# MBoard.net
KiCad netlist of a schematic drawn in Altium Designer
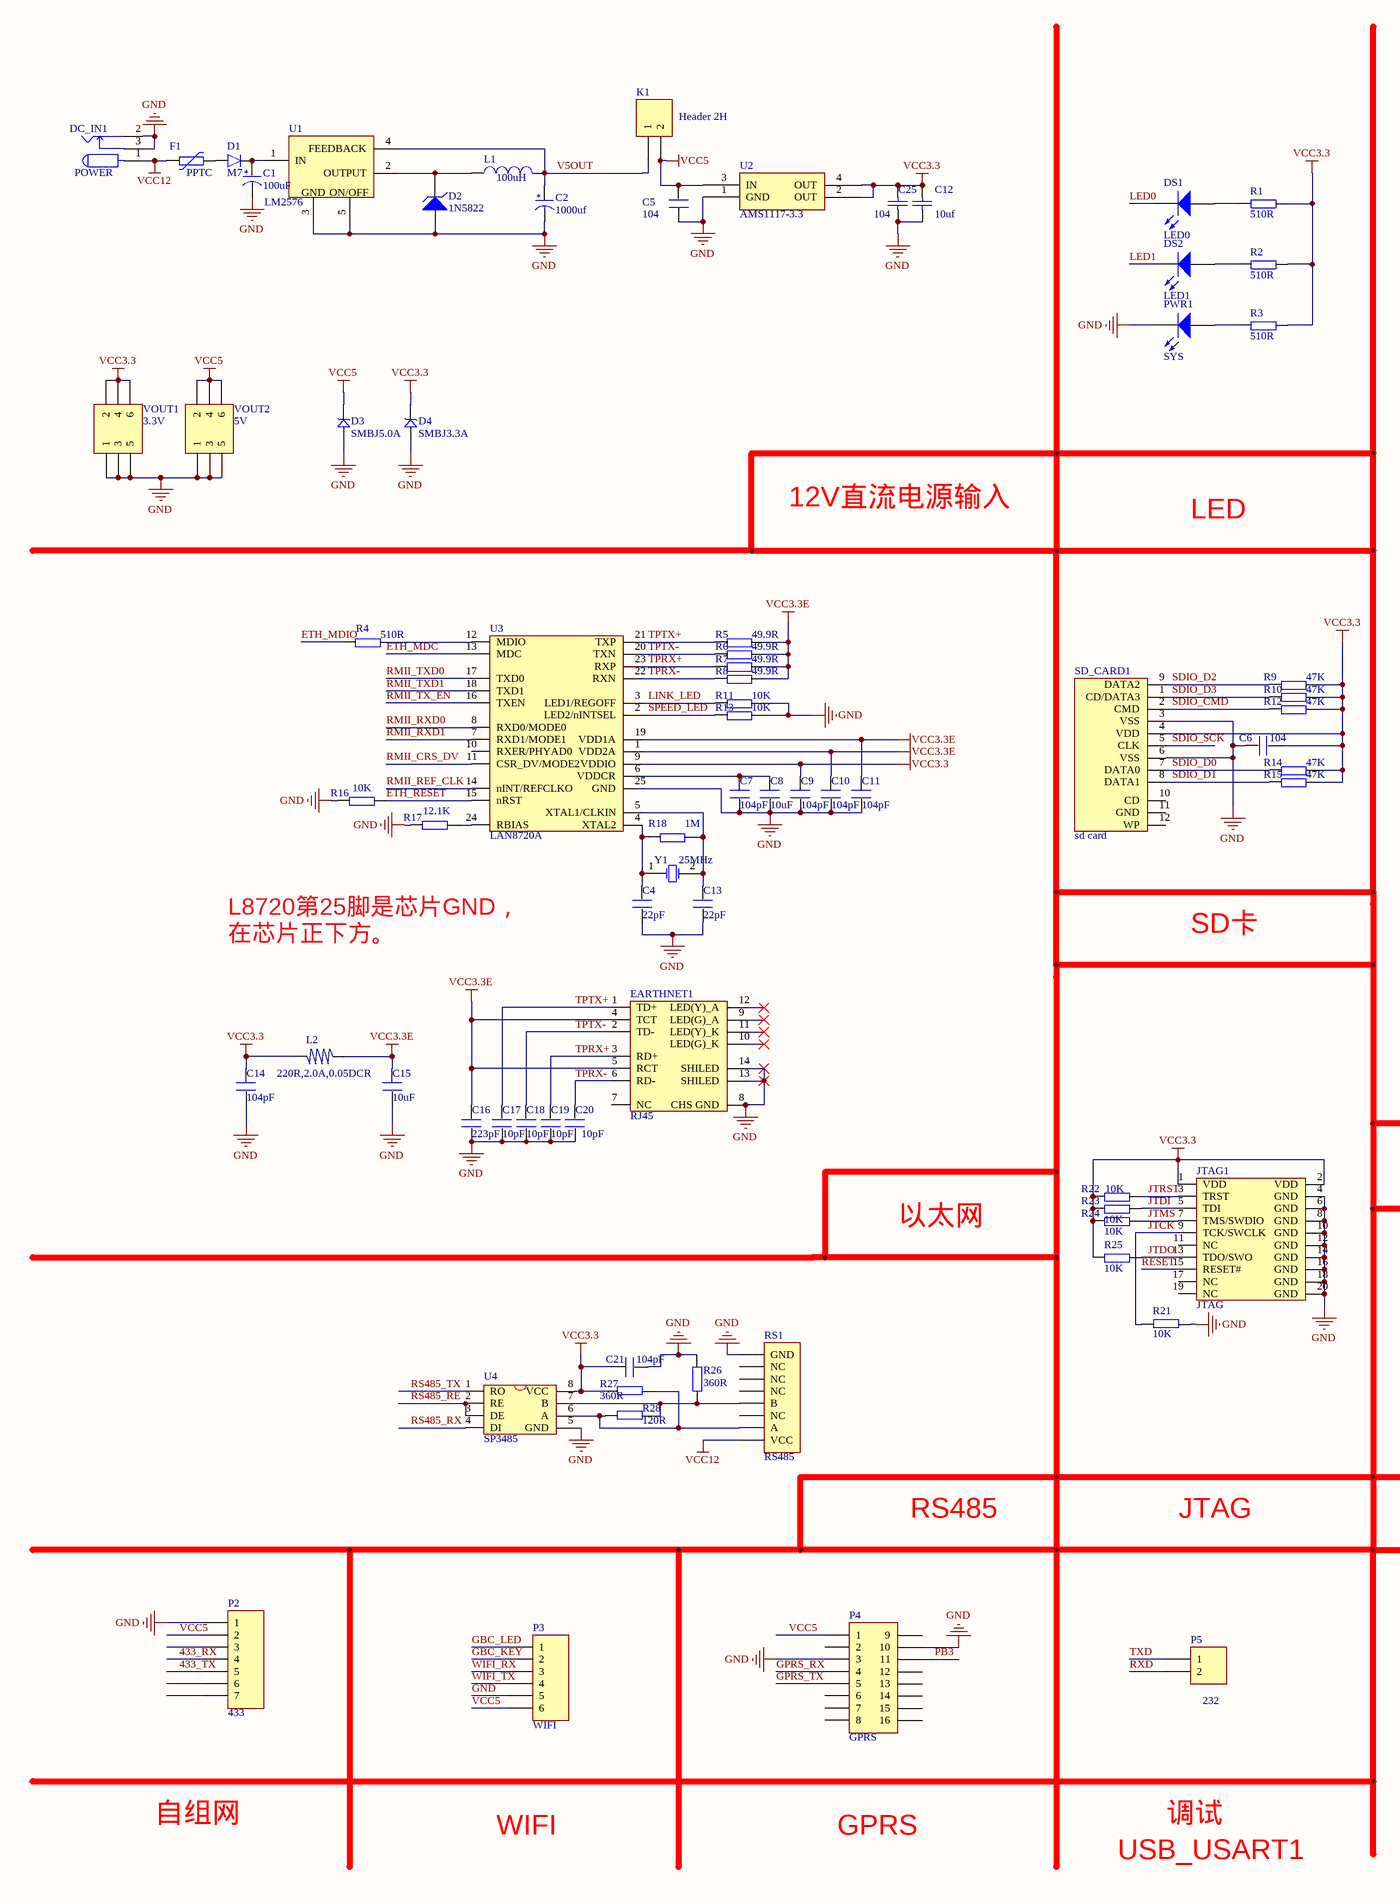
[diagram p0: MBoard.SchDoc, left]
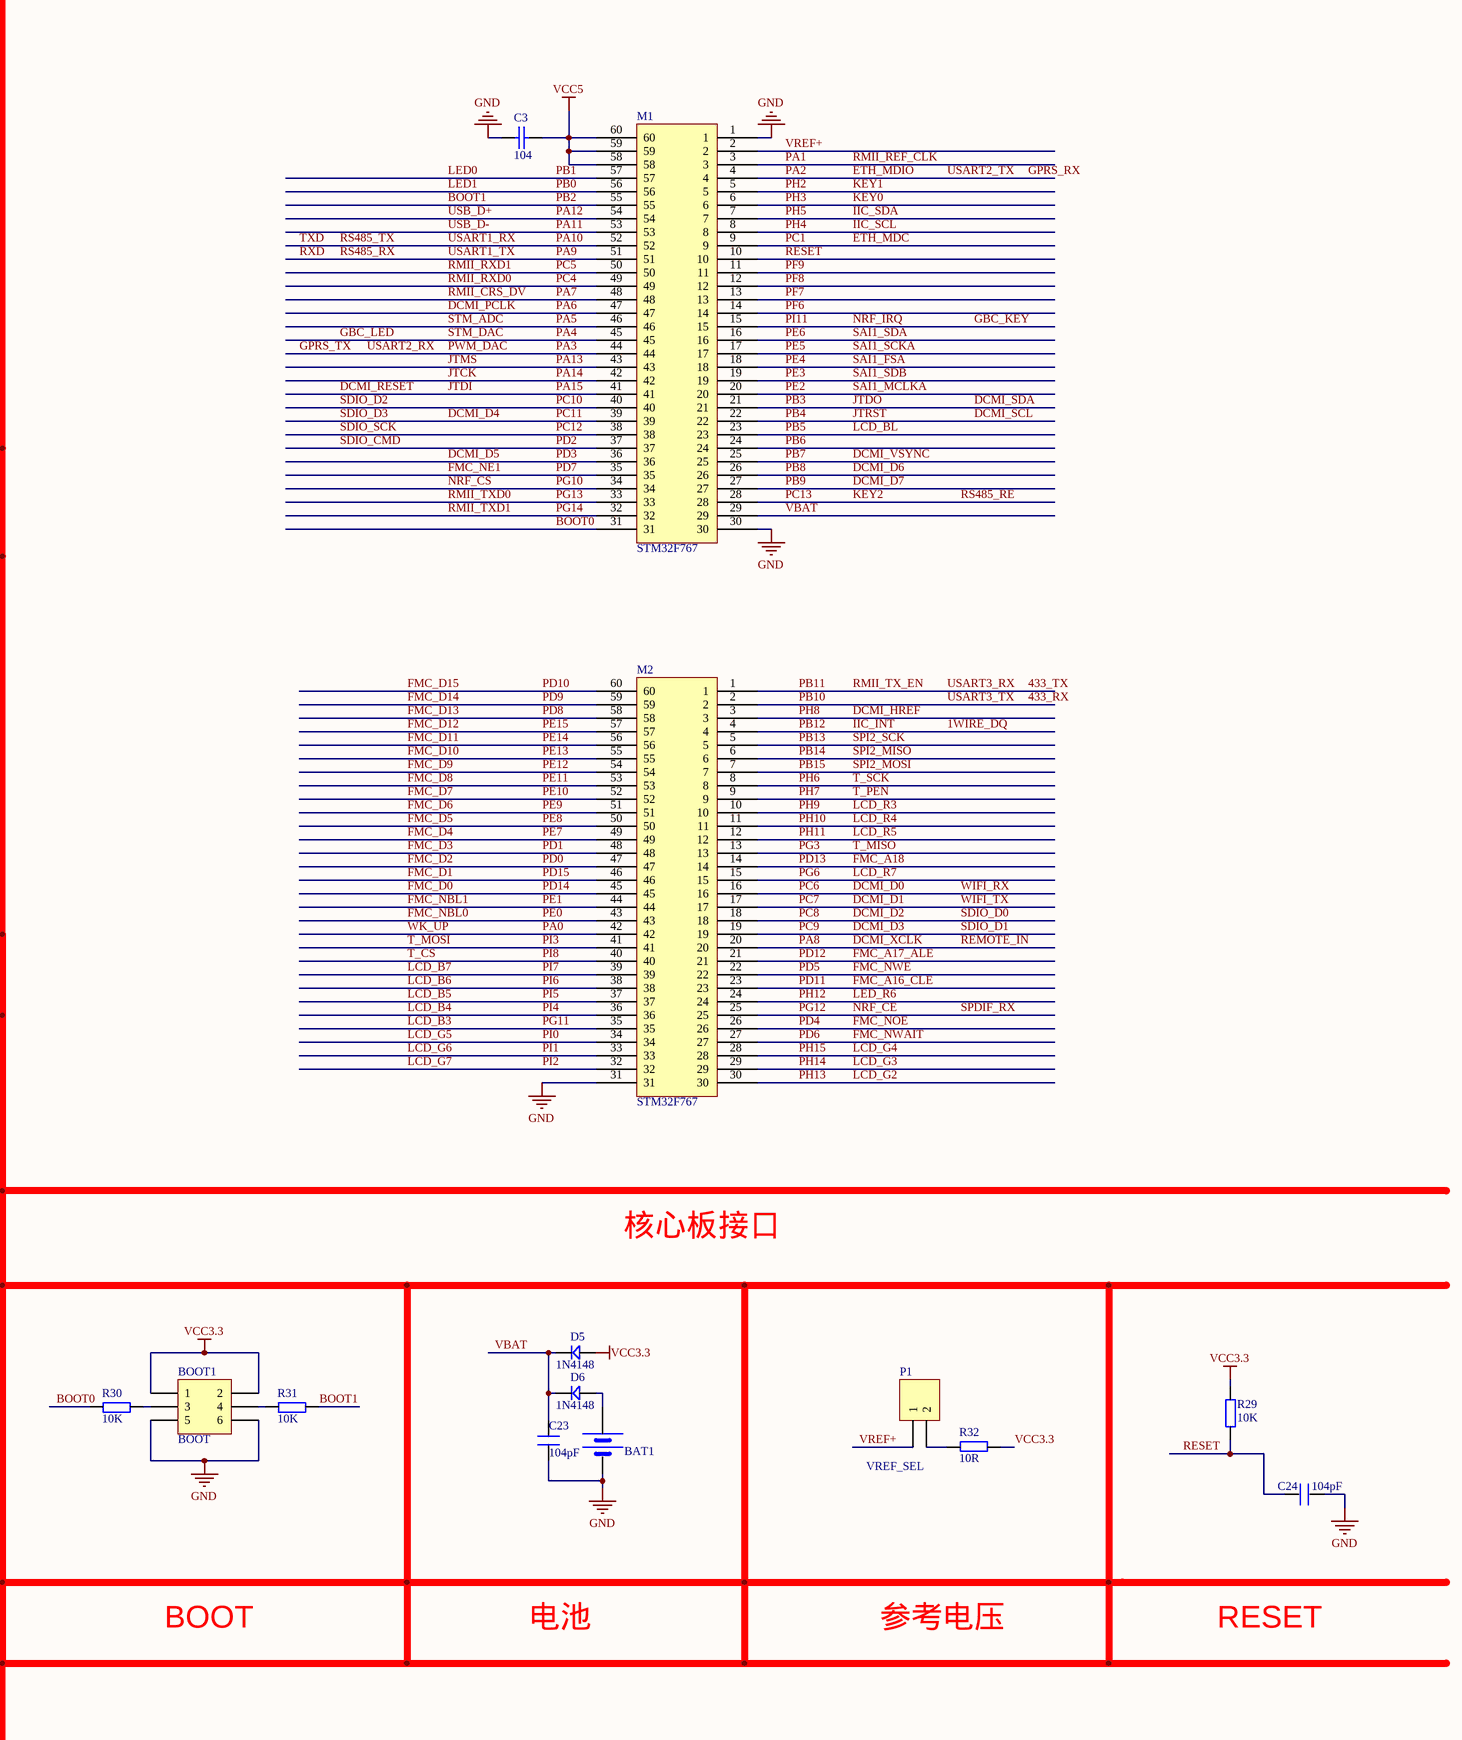
[diagram p1: MBoard.SchDoc, right]

(export (version "E")
  (design (tool "Eeschema 10.0.6"))
  (components
    (comp (ref "BAT1")
      (value "BATT")
      (footprint "BATM")
      (libsource (lib "Explorer STM32F407封装库2") (part "BAT"))
    )
    (comp (ref "BOOT1")
      (value "BOOT")
      (footprint "HDR2X3")
      (description "Header, 3-Pin, Dual row")
      (libsource (lib "Explorer STM32F407封装库2") (part "Header 3X2"))
    )
    (comp (ref "C1") (value "100uF") (footprint "CC6.56.5") (libsource (lib "EXPLORER") (part "CAP")))
    (comp (ref "C2") (value "1000uf") (footprint "CC6.56.5") (libsource (lib "EXPLORER") (part "CAP")))
    (comp (ref "C3")
      (value "104")
      (footprint "c0603")
      (description "Capacitor")
      (fields (field (name "Comment") "Cap"))
      (libsource (lib "Miscellaneous Devices") (part "Cap"))
    )
    (comp (ref "C4") (value "22pF") (footprint "C0603") (libsource (lib "Explorer STM32F407封装库2") (part "C")))
    (comp (ref "C5") (value "104") (footprint "C0603") (libsource (lib "Explorer STM32F407封装库2") (part "C")))
    (comp (ref "C6") (value "104") (footprint "C0603") (libsource (lib "Explorer STM32F407封装库2") (part "C")))
    (comp (ref "C7")
      (value "104pF")
      (footprint "C0603")
      (libsource (lib "Explorer STM32F407封装库2") (part "C"))
    )
    (comp (ref "C8") (value "10uF") (footprint "C0805") (libsource (lib "Explorer STM32F407封装库2") (part "C")))
    (comp (ref "C9")
      (value "104pF")
      (footprint "C0603")
      (libsource (lib "Explorer STM32F407封装库2") (part "C"))
    )
    (comp (ref "C10")
      (value "104pF")
      (footprint "C0603")
      (libsource (lib "Explorer STM32F407封装库2") (part "C"))
    )
    (comp (ref "C11")
      (value "104pF")
      (footprint "C0603")
      (libsource (lib "Explorer STM32F407封装库2") (part "C"))
    )
    (comp (ref "C12")
      (value "10uf")
      (footprint "C0603")
      (description "50V/8.2u/0805")
      (libsource (lib "Miscellaneous Devices") (part "Cap"))
    )
    (comp (ref "C13")
      (value "22pF")
      (footprint "C0603")
      (libsource (lib "Explorer STM32F407封装库2") (part "C"))
    )
    (comp (ref "C14")
      (value "104pF")
      (footprint "C0603")
      (libsource (lib "Explorer STM32F407封装库2") (part "C"))
    )
    (comp (ref "C15")
      (value "10uF")
      (footprint "C0805")
      (libsource (lib "Explorer STM32F407封装库2") (part "C"))
    )
    (comp (ref "C16")
      (value "223pF")
      (footprint "C0603")
      (libsource (lib "Explorer STM32F407封装库2") (part "C"))
    )
    (comp (ref "C17")
      (value "10pF")
      (footprint "C0603")
      (libsource (lib "Explorer STM32F407封装库2") (part "C"))
    )
    (comp (ref "C18")
      (value "10pF")
      (footprint "C0603")
      (libsource (lib "Explorer STM32F407封装库2") (part "C"))
    )
    (comp (ref "C19")
      (value "10pF")
      (footprint "C0603")
      (libsource (lib "Explorer STM32F407封装库2") (part "C"))
    )
    (comp (ref "C20")
      (value "10pF")
      (footprint "C0603")
      (libsource (lib "Explorer STM32F407封装库2") (part "C"))
    )
    (comp (ref "C21")
      (value "104pF")
      (footprint "C0603")
      (libsource (lib "Explorer STM32F407封装库2") (part "C"))
    )
    (comp (ref "C23")
      (value "104pF")
      (footprint "C0603")
      (libsource (lib "Explorer STM32F407封装库2") (part "C"))
    )
    (comp (ref "C24")
      (value "104pF")
      (footprint "C0603")
      (libsource (lib "Explorer STM32F407封装库2") (part "C"))
    )
    (comp (ref "C25")
      (value "104")
      (footprint "c0603")
      (description "Capacitor")
      (fields (field (name "Comment") "Cap"))
      (libsource (lib "Miscellaneous Devices") (part "Cap"))
    )
    (comp (ref "D1") (value "M7") (footprint "SMA (DO-214AC)") (libsource (lib "基本元件") (part "M7")))
    (comp (ref "D2")
      (value "1N5822")
      (footprint "smb do214aa")
      (description "Zener Diode")
      (libsource (lib "Miscellaneous Devices") (part "D Zener"))
    )
    (comp (ref "D3")
      (value "SMBJ5.0A")
      (footprint "SMBJ")
      (description "TVS")
      (libsource (lib "Explorer STM32F407封装库2") (part "SMBJ"))
    )
    (comp (ref "D4")
      (value "SMBJ3.3A")
      (footprint "SMBJ")
      (description "TVS")
      (libsource (lib "Explorer STM32F407封装库2") (part "SMBJ"))
    )
    (comp (ref "D5")
      (value "1N4148")
      (footprint "Diode_MELF(1206)")
      (libsource (lib "Explorer STM32F407封装库2") (part "D"))
    )
    (comp (ref "D6")
      (value "1N4148")
      (footprint "Diode_MELF(1206)")
      (libsource (lib "Explorer STM32F407封装库2") (part "D"))
    )
    (comp (ref "DC_IN1")
      (value "POWER")
      (footprint "DC10B")
      (libsource (lib "Explorer STM32F407封装库2") (part "POW"))
    )
    (comp (ref "DS1")
      (value "LED0")
      (footprint "SMDLED")
      (description "Typical RED, GREEN, YELLOW, AMBER GaAs LED")
      (libsource (lib "Explorer STM32F407封装库2") (part "LED2"))
    )
    (comp (ref "DS2")
      (value "LED1")
      (footprint "SMDLED")
      (description "Typical RED, GREEN, YELLOW, AMBER GaAs LED")
      (libsource (lib "Explorer STM32F407封装库2") (part "LED2"))
    )
    (comp (ref "EARTHNET1")
      (value "RJ45")
      (footprint "RJ45")
      (libsource (lib "Explorer STM32F407封装库2") (part "HR911105"))
    )
    (comp (ref "F1") (value "PPTC") (footprint "1206") (libsource (lib "基本") (part "PPTC")))
    (comp (ref "JTAG1")
      (value "JTAG")
      (footprint "JTAG_20")
      (libsource (lib "Explorer STM32F407封装库2") (part "JTAG"))
    )
    (comp (ref "K1")
      (value "Header 2H")
      (footprint "HDR1X2")
      (description "Header, 2-Pin, Right Angle")
      (libsource (lib "Miscellaneous Connectors") (part "Header 2H"))
    )
    (comp (ref "L1")
      (value "100uH")
      (footprint "l1212")
      (description "Inductor")
      (libsource (lib "Miscellaneous Devices") (part "Inductor"))
    )
    (comp (ref "L2")
      (value "220R,2.0A,0.05DCR")
      (footprint "R0603")
      (libsource (lib "Explorer STM32F407封装库2") (part "L"))
    )
    (comp (ref "M1") (value "STM32F767") (footprint "60pin") (libsource (lib "ZS-005") (part "J1")))
    (comp (ref "M2") (value "STM32F767") (footprint "60pin") (libsource (lib "ZS-005") (part "J1")))
    (comp (ref "P1")
      (value "VREF_SEL")
      (footprint "HDR1X2")
      (description "Header, 2-Pin")
      (libsource (lib "Explorer STM32F407封装库2") (part "Header 2"))
    )
    (comp (ref "P2")
      (value "433")
      (footprint "HDR1X7")
      (description "Header, 7-Pin")
      (libsource (lib "Miscellaneous Connectors") (part "Header 7"))
    )
    (comp (ref "P3")
      (value "WIFI")
      (footprint "HDR1X6")
      (description "Header, 6-Pin, Right Angle")
      (libsource (lib "Miscellaneous Connectors") (part "Header 6H"))
    )
    (comp (ref "P4")
      (value "GPRS")
      (footprint "GPRS")
      (description "Header, 8-Pin, Dual row")
      (libsource (lib "Miscellaneous Connectors") (part "Header 8X2A"))
    )
    (comp (ref "P5")
      (value "232")
      (footprint "HDR1X2")
      (description "Header, 2-Pin")
      (libsource (lib "Miscellaneous Connectors") (part "Header 2"))
    )
    (comp (ref "PWR1")
      (value "SYS")
      (footprint "SMDLED")
      (description "Typical RED, GREEN, YELLOW, AMBER GaAs LED")
      (libsource (lib "Explorer STM32F407封装库2") (part "LED2"))
    )
    (comp (ref "R1") (value "510R") (footprint "R0603") (libsource (lib "Explorer STM32F407封装库2") (part "R")))
    (comp (ref "R2") (value "510R") (footprint "R0603") (libsource (lib "Explorer STM32F407封装库2") (part "R")))
    (comp (ref "R3") (value "510R") (footprint "R0603") (libsource (lib "Explorer STM32F407封装库2") (part "R")))
    (comp (ref "R4") (value "510R") (footprint "R0603") (libsource (lib "Explorer STM32F407封装库2") (part "R")))
    (comp (ref "R5")
      (value "49.9R")
      (footprint "R0603")
      (libsource (lib "Explorer STM32F407封装库2") (part "R"))
    )
    (comp (ref "R6")
      (value "49.9R")
      (footprint "R0603")
      (libsource (lib "Explorer STM32F407封装库2") (part "R"))
    )
    (comp (ref "R7")
      (value "49.9R")
      (footprint "R0603")
      (libsource (lib "Explorer STM32F407封装库2") (part "R"))
    )
    (comp (ref "R8")
      (value "49.9R")
      (footprint "R0603")
      (libsource (lib "Explorer STM32F407封装库2") (part "R"))
    )
    (comp (ref "R9") (value "47K") (footprint "R0603") (libsource (lib "Explorer STM32F407封装库2") (part "R")))
    (comp (ref "R10") (value "47K") (footprint "R0603") (libsource (lib "Explorer STM32F407封装库2") (part "R")))
    (comp (ref "R11") (value "10K") (footprint "R0603") (libsource (lib "Explorer STM32F407封装库2") (part "R")))
    (comp (ref "R12") (value "47K") (footprint "R0603") (libsource (lib "Explorer STM32F407封装库2") (part "R")))
    (comp (ref "R13") (value "10K") (footprint "R0603") (libsource (lib "Explorer STM32F407封装库2") (part "R")))
    (comp (ref "R14") (value "47K") (footprint "R0603") (libsource (lib "Explorer STM32F407封装库2") (part "R")))
    (comp (ref "R15") (value "47K") (footprint "R0603") (libsource (lib "Explorer STM32F407封装库2") (part "R")))
    (comp (ref "R16") (value "10K") (footprint "R0603") (libsource (lib "Explorer STM32F407封装库2") (part "R")))
    (comp (ref "R17")
      (value "12.1K")
      (footprint "R0603")
      (libsource (lib "Explorer STM32F407封装库2") (part "R"))
    )
    (comp (ref "R18") (value "1M") (footprint "R0603") (libsource (lib "Explorer STM32F407封装库2") (part "R")))
    (comp (ref "R21") (value "10K") (footprint "R0603") (libsource (lib "Explorer STM32F407封装库2") (part "R")))
    (comp (ref "R22") (value "10K") (footprint "R0603") (libsource (lib "Explorer STM32F407封装库2") (part "R")))
    (comp (ref "R23") (value "10K") (footprint "R0603") (libsource (lib "Explorer STM32F407封装库2") (part "R")))
    (comp (ref "R24") (value "10K") (footprint "R0603") (libsource (lib "Explorer STM32F407封装库2") (part "R")))
    (comp (ref "R25") (value "10K") (footprint "R0603") (libsource (lib "Explorer STM32F407封装库2") (part "R")))
    (comp (ref "R26")
      (value "360R")
      (footprint "R0603")
      (libsource (lib "Explorer STM32F407封装库2") (part "R"))
    )
    (comp (ref "R27")
      (value "360R")
      (footprint "R0603")
      (libsource (lib "Explorer STM32F407封装库2") (part "R"))
    )
    (comp (ref "R28")
      (value "120R")
      (footprint "R0603")
      (libsource (lib "Explorer STM32F407封装库2") (part "R"))
    )
    (comp (ref "R29") (value "10K") (footprint "R0603") (libsource (lib "Explorer STM32F407封装库2") (part "R")))
    (comp (ref "R30") (value "10K") (footprint "R0603") (libsource (lib "Explorer STM32F407封装库2") (part "R")))
    (comp (ref "R31") (value "10K") (footprint "R0603") (libsource (lib "Explorer STM32F407封装库2") (part "R")))
    (comp (ref "R32") (value "10R") (footprint "R0603") (libsource (lib "Explorer STM32F407封装库2") (part "R")))
    (comp (ref "RS1")
      (value "RS485")
      (footprint "RJ45")
      (description "Header, 8-Pin")
      (libsource (lib "Miscellaneous Connectors") (part "Header 8"))
    )
    (comp (ref "SD_CARD1")
      (value "sd card")
      (footprint "SDCARD_L")
      (libsource (lib "Explorer STM32F407封装库2") (part "sd card"))
    )
    (comp (ref "U1") (value "LM2576") (footprint "TO-263-5") (libsource (lib "STM32") (part "LM2576")))
    (comp (ref "U2")
      (value "AMS1117-3.3")
      (footprint "AMS1117-3.3")
      (libsource (lib "AMS1117-3.3") (part "AMS1117-3.3"))
    )
    (comp (ref "U3")
      (value "LAN8720A")
      (footprint "QFN24")
      (description "ETH PHY")
      (libsource (lib "Explorer STM32F407封装库2") (part "LAN8720"))
    )
    (comp (ref "U4")
      (value "SP3485")
      (footprint "SOP-8")
      (libsource (lib "Explorer STM32F407封装库2") (part "MAX3485"))
    )
    (comp (ref "VOUT1")
      (value "3.3V")
      (footprint "HDR2X3")
      (description "Header, 3-Pin, Dual row")
      (libsource (lib "") (part "Header 3X2_1"))
    )
    (comp (ref "VOUT2")
      (value "5V")
      (footprint "HDR2X3")
      (description "Header, 3-Pin, Dual row")
      (libsource (lib "") (part "Header 3X2_1"))
    )
    (comp (ref "Y1")
      (value "25MHz")
      (footprint "XTAL_US")
      (description "Crystal Oscillator")
      (libsource (lib "Explorer STM32F407封装库2") (part "XTAL"))
    )
  )
  (nets
    (net (code "1") (name "/1WIRE_DQ") (class "Default")
      (node (ref "M2") (pin "4") (pinfunction "4_4") (pintype "passive"))
    )
    (net (code "2") (name "/433_RX") (class "Default")
      (node (ref "M2") (pin "2") (pinfunction "2_2") (pintype "passive"))
      (node (ref "P2") (pin "4") (pinfunction "4_4") (pintype "passive"))
    )
    (net (code "3") (name "/433_TX") (class "Default")
      (node (ref "M2") (pin "1") (pinfunction "1_1") (pintype "passive"))
      (node (ref "P2") (pin "5") (pinfunction "5_5") (pintype "passive"))
      (node (ref "U3") (pin "16") (pinfunction "TXEN_16") (pintype "passive"))
    )
    (net (code "4") (name "/BOOT0") (class "Default")
      (node (ref "M1") (pin "31") (pinfunction "31_31") (pintype "passive"))
      (node (ref "R30") (pin "1") (pintype "passive"))
    )
    (net (code "5") (name "/BOOT1") (class "Default")
      (node (ref "M1") (pin "55") (pinfunction "55_55") (pintype "passive"))
      (node (ref "R31") (pin "2") (pintype "passive"))
    )
    (net (code "6") (name "/DCMI_D0") (class "Default")
      (node (ref "M2") (pin "16") (pinfunction "16_16") (pintype "passive"))
      (node (ref "P3") (pin "3") (pinfunction "3_3") (pintype "passive"))
    )
    (net (code "7") (name "/DCMI_D1") (class "Default")
      (node (ref "M2") (pin "17") (pinfunction "17_17") (pintype "passive"))
      (node (ref "P3") (pin "4") (pinfunction "4_4") (pintype "passive"))
    )
    (net (code "8") (name "/DCMI_D2") (class "Default")
      (node (ref "M2") (pin "18") (pinfunction "18_18") (pintype "passive"))
      (node (ref "R14") (pin "1") (pintype "passive"))
      (node (ref "SD_CARD1") (pin "7") (pinfunction "DATA0_7") (pintype "passive"))
    )
    (net (code "9") (name "/DCMI_D3") (class "Default")
      (node (ref "M2") (pin "19") (pinfunction "19_19") (pintype "passive"))
      (node (ref "R15") (pin "1") (pintype "passive"))
      (node (ref "SD_CARD1") (pin "8") (pinfunction "DATA1_8") (pintype "passive"))
    )
    (net (code "10") (name "/DCMI_D4") (class "Default")
      (node (ref "M1") (pin "39") (pinfunction "39_39") (pintype "passive"))
      (node (ref "R10") (pin "1") (pintype "passive"))
      (node (ref "SD_CARD1") (pin "1") (pinfunction "CD/DATA3_1") (pintype "passive"))
    )
    (net (code "11") (name "/DCMI_D5") (class "Default")
      (node (ref "M1") (pin "36") (pinfunction "36_36") (pintype "passive"))
    )
    (net (code "12") (name "/DCMI_D6") (class "Default")
      (node (ref "M1") (pin "26") (pinfunction "26_26") (pintype "passive"))
    )
    (net (code "13") (name "/DCMI_D7") (class "Default")
      (node (ref "M1") (pin "27") (pinfunction "27_27") (pintype "passive"))
    )
    (net (code "14") (name "/DCMI_HREF") (class "Default")
      (node (ref "M2") (pin "3") (pinfunction "3_3") (pintype "passive"))
    )
    (net (code "15") (name "/DCMI_PCLK") (class "Default")
      (node (ref "M1") (pin "47") (pinfunction "47_47") (pintype "passive"))
    )
    (net (code "16") (name "/DCMI_RESET") (class "Default")
      (node (ref "JTAG1") (pin "5") (pinfunction "TDI_5") (pintype "passive"))
      (node (ref "M1") (pin "41") (pinfunction "41_41") (pintype "passive"))
      (node (ref "R23") (pin "2") (pintype "passive"))
    )
    (net (code "17") (name "/DCMI_SCL") (class "Default")
      (node (ref "JTAG1") (pin "3") (pinfunction "TRST_3") (pintype "passive"))
      (node (ref "M1") (pin "22") (pinfunction "22_22") (pintype "passive"))
      (node (ref "R22") (pin "2") (pintype "passive"))
    )
    (net (code "18") (name "/DCMI_SDA") (class "Default")
      (node (ref "JTAG1") (pin "13") (pinfunction "TDO/SWO_13") (pintype "passive"))
      (node (ref "M1") (pin "21") (pinfunction "21_21") (pintype "passive"))
      (node (ref "P4") (pin "11") (pinfunction "11_11") (pintype "passive"))
      (node (ref "R25") (pin "2") (pintype "passive"))
    )
    (net (code "19") (name "/DCMI_VSYNC") (class "Default")
      (node (ref "M1") (pin "25") (pinfunction "25_25") (pintype "passive"))
    )
    (net (code "20") (name "/DCMI_XCLK") (class "Default")
      (node (ref "M2") (pin "20") (pinfunction "20_20") (pintype "passive"))
    )
    (net (code "21") (name "/ETH_MDC") (class "Default")
      (node (ref "M1") (pin "9") (pinfunction "9_9") (pintype "passive"))
      (node (ref "U3") (pin "13") (pinfunction "MDC_13") (pintype "passive"))
    )
    (net (code "22") (name "/ETH_MDIO") (class "Default")
      (node (ref "M1") (pin "4") (pinfunction "4_4") (pintype "passive"))
      (node (ref "P4") (pin "4") (pinfunction "4_4") (pintype "passive"))
      (node (ref "R4") (pin "1") (pintype "passive"))
    )
    (net (code "23") (name "/ETH_RESET") (class "Default")
      (node (ref "R16") (pin "2") (pintype "passive"))
      (node (ref "U3") (pin "15") (pinfunction "nRST_15") (pintype "passive"))
    )
    (net (code "24") (name "/FMC_A16_CLE") (class "Default")
      (node (ref "M2") (pin "23") (pinfunction "23_23") (pintype "passive"))
    )
    (net (code "25") (name "/FMC_A17_ALE") (class "Default")
      (node (ref "M2") (pin "21") (pinfunction "21_21") (pintype "passive"))
    )
    (net (code "26") (name "/FMC_A18") (class "Default")
      (node (ref "M2") (pin "14") (pinfunction "14_14") (pintype "passive"))
    )
    (net (code "27") (name "/FMC_D0") (class "Default")
      (node (ref "M2") (pin "45") (pinfunction "45_45") (pintype "passive"))
    )
    (net (code "28") (name "/FMC_D1") (class "Default")
      (node (ref "M2") (pin "46") (pinfunction "46_46") (pintype "passive"))
    )
    (net (code "29") (name "/FMC_D2") (class "Default")
      (node (ref "M2") (pin "47") (pinfunction "47_47") (pintype "passive"))
    )
    (net (code "30") (name "/FMC_D3") (class "Default")
      (node (ref "M2") (pin "48") (pinfunction "48_48") (pintype "passive"))
    )
    (net (code "31") (name "/FMC_D4") (class "Default")
      (node (ref "M2") (pin "49") (pinfunction "49_49") (pintype "passive"))
    )
    (net (code "32") (name "/FMC_D5") (class "Default")
      (node (ref "M2") (pin "50") (pinfunction "50_50") (pintype "passive"))
    )
    (net (code "33") (name "/FMC_D6") (class "Default")
      (node (ref "M2") (pin "51") (pinfunction "51_51") (pintype "passive"))
    )
    (net (code "34") (name "/FMC_D7") (class "Default")
      (node (ref "M2") (pin "52") (pinfunction "52_52") (pintype "passive"))
    )
    (net (code "35") (name "/FMC_D8") (class "Default")
      (node (ref "M2") (pin "53") (pinfunction "53_53") (pintype "passive"))
    )
    (net (code "36") (name "/FMC_D9") (class "Default")
      (node (ref "M2") (pin "54") (pinfunction "54_54") (pintype "passive"))
    )
    (net (code "37") (name "/FMC_D10") (class "Default")
      (node (ref "M2") (pin "55") (pinfunction "55_55") (pintype "passive"))
    )
    (net (code "38") (name "/FMC_D11") (class "Default")
      (node (ref "M2") (pin "56") (pinfunction "56_56") (pintype "passive"))
    )
    (net (code "39") (name "/FMC_D12") (class "Default")
      (node (ref "M2") (pin "57") (pinfunction "57_57") (pintype "passive"))
    )
    (net (code "40") (name "/FMC_D13") (class "Default")
      (node (ref "M2") (pin "58") (pinfunction "58_58") (pintype "passive"))
    )
    (net (code "41") (name "/FMC_D14") (class "Default")
      (node (ref "M2") (pin "59") (pinfunction "59_59") (pintype "passive"))
    )
    (net (code "42") (name "/FMC_D15") (class "Default")
      (node (ref "M2") (pin "60") (pinfunction "60_60") (pintype "passive"))
    )
    (net (code "43") (name "/FMC_NBL0") (class "Default")
      (node (ref "M2") (pin "43") (pinfunction "43_43") (pintype "passive"))
    )
    (net (code "44") (name "/FMC_NBL1") (class "Default")
      (node (ref "M2") (pin "44") (pinfunction "44_44") (pintype "passive"))
    )
    (net (code "45") (name "/FMC_NE1") (class "Default")
      (node (ref "M1") (pin "35") (pinfunction "35_35") (pintype "passive"))
    )
    (net (code "46") (name "/FMC_NOE") (class "Default")
      (node (ref "M2") (pin "26") (pinfunction "26_26") (pintype "passive"))
    )
    (net (code "47") (name "/FMC_NWAIT") (class "Default")
      (node (ref "M2") (pin "27") (pinfunction "27_27") (pintype "passive"))
    )
    (net (code "48") (name "/FMC_NWE") (class "Default")
      (node (ref "M2") (pin "22") (pinfunction "22_22") (pintype "passive"))
    )
    (net (code "49") (name "/GBC_KEY") (class "Default")
      (node (ref "M1") (pin "15") (pinfunction "15_15") (pintype "passive"))
      (node (ref "P3") (pin "2") (pinfunction "2_2") (pintype "passive"))
    )
    (net (code "50") (name "/GBC_LED") (class "Default")
      (node (ref "M1") (pin "45") (pinfunction "45_45") (pintype "passive"))
      (node (ref "P3") (pin "1") (pinfunction "1_1") (pintype "passive"))
    )
    (net (code "51") (name "/GPRS_TX") (class "Default")
      (node (ref "M1") (pin "44") (pinfunction "44_44") (pintype "passive"))
      (node (ref "P4") (pin "5") (pinfunction "5_5") (pintype "passive"))
    )
    (net (code "52") (name "/IIC_SCL") (class "Default")
      (node (ref "M1") (pin "8") (pinfunction "8_8") (pintype "passive"))
    )
    (net (code "53") (name "/IIC_SDA") (class "Default")
      (node (ref "M1") (pin "7") (pinfunction "7_7") (pintype "passive"))
    )
    (net (code "54") (name "/JTCK") (class "Default")
      (node (ref "JTAG1") (pin "9") (pinfunction "TCK/SWCLK_9") (pintype "passive"))
      (node (ref "M1") (pin "42") (pinfunction "42_42") (pintype "passive"))
      (node (ref "R21") (pin "2") (pintype "passive"))
    )
    (net (code "55") (name "/JTMS") (class "Default")
      (node (ref "JTAG1") (pin "7") (pinfunction "TMS/SWDIO_7") (pintype "passive"))
      (node (ref "M1") (pin "43") (pinfunction "43_43") (pintype "passive"))
      (node (ref "R24") (pin "2") (pintype "passive"))
    )
    (net (code "56") (name "/KEY0") (class "Default")
      (node (ref "M1") (pin "6") (pinfunction "6_6") (pintype "passive"))
    )
    (net (code "57") (name "/KEY1") (class "Default")
      (node (ref "M1") (pin "5") (pinfunction "5_5") (pintype "passive"))
    )
    (net (code "58") (name "/KEY2") (class "Default")
      (node (ref "M1") (pin "28") (pinfunction "28_28") (pintype "passive"))
      (node (ref "U4") (pin "2") (pinfunction "RE_2") (pintype "passive"))
      (node (ref "U4") (pin "3") (pinfunction "DE_3") (pintype "passive"))
    )
    (net (code "59") (name "/LCD_B3") (class "Default")
      (node (ref "M2") (pin "35") (pinfunction "35_35") (pintype "passive"))
    )
    (net (code "60") (name "/LCD_B4") (class "Default")
      (node (ref "M2") (pin "36") (pinfunction "36_36") (pintype "passive"))
    )
    (net (code "61") (name "/LCD_B5") (class "Default")
      (node (ref "M2") (pin "37") (pinfunction "37_37") (pintype "passive"))
    )
    (net (code "62") (name "/LCD_B6") (class "Default")
      (node (ref "M2") (pin "38") (pinfunction "38_38") (pintype "passive"))
    )
    (net (code "63") (name "/LCD_B7") (class "Default")
      (node (ref "M2") (pin "39") (pinfunction "39_39") (pintype "passive"))
    )
    (net (code "64") (name "/LCD_BL") (class "Default")
      (node (ref "M1") (pin "23") (pinfunction "23_23") (pintype "passive"))
    )
    (net (code "65") (name "/LCD_G2") (class "Default")
      (node (ref "M2") (pin "30") (pinfunction "30_30") (pintype "passive"))
    )
    (net (code "66") (name "/LCD_G3") (class "Default")
      (node (ref "M2") (pin "29") (pinfunction "29_29") (pintype "passive"))
    )
    (net (code "67") (name "/LCD_G4") (class "Default")
      (node (ref "M2") (pin "28") (pinfunction "28_28") (pintype "passive"))
    )
    (net (code "68") (name "/LCD_G5") (class "Default")
      (node (ref "M2") (pin "34") (pinfunction "34_34") (pintype "passive"))
    )
    (net (code "69") (name "/LCD_G6") (class "Default")
      (node (ref "M2") (pin "33") (pinfunction "33_33") (pintype "passive"))
    )
    (net (code "70") (name "/LCD_G7") (class "Default")
      (node (ref "M2") (pin "32") (pinfunction "32_32") (pintype "passive"))
    )
    (net (code "71") (name "/LCD_R3") (class "Default")
      (node (ref "M2") (pin "10") (pinfunction "10_10") (pintype "passive"))
    )
    (net (code "72") (name "/LCD_R4") (class "Default")
      (node (ref "M2") (pin "11") (pinfunction "11_11") (pintype "passive"))
    )
    (net (code "73") (name "/LCD_R5") (class "Default")
      (node (ref "M2") (pin "12") (pinfunction "12_12") (pintype "passive"))
    )
    (net (code "74") (name "/LCD_R7") (class "Default")
      (node (ref "M2") (pin "15") (pinfunction "15_15") (pintype "passive"))
    )
    (net (code "75") (name "/LED0") (class "Default")
      (node (ref "DS1") (pin "2") (pinfunction "K_2") (pintype "passive"))
      (node (ref "M1") (pin "57") (pinfunction "57_57") (pintype "passive"))
    )
    (net (code "76") (name "/LED1") (class "Default")
      (node (ref "DS2") (pin "2") (pinfunction "K_2") (pintype "passive"))
      (node (ref "M1") (pin "56") (pinfunction "56_56") (pintype "passive"))
    )
    (net (code "77") (name "/LED_R6") (class "Default")
      (node (ref "M2") (pin "24") (pinfunction "24_24") (pintype "passive"))
    )
    (net (code "78") (name "/LINK_LED") (class "Default")
      (node (ref "R11") (pin "1") (pintype "passive"))
      (node (ref "U3") (pin "3") (pinfunction "LED1/REGOFF_3") (pintype "passive"))
    )
    (net (code "79") (name "/NRF_CE") (class "Default")
      (node (ref "M2") (pin "25") (pinfunction "25_25") (pintype "passive"))
    )
    (net (code "80") (name "/NRF_CS") (class "Default")
      (node (ref "M1") (pin "34") (pinfunction "34_34") (pintype "passive"))
    )
    (net (code "81") (name "/PA0") (class "Default")
      (node (ref "M2") (pin "42") (pinfunction "42_42") (pintype "passive"))
    )
    (net (code "82") (name "/PA1") (class "Default")
      (node (ref "M1") (pin "3") (pinfunction "3_3") (pintype "passive"))
      (node (ref "U3") (pin "14") (pinfunction "nINT/REFCLKO_14") (pintype "passive"))
    )
    (net (code "83") (name "/PA5") (class "Default")
      (node (ref "M1") (pin "46") (pinfunction "46_46") (pintype "passive"))
    )
    (net (code "84") (name "/PA7") (class "Default")
      (node (ref "M1") (pin "48") (pinfunction "48_48") (pintype "passive"))
      (node (ref "U3") (pin "11") (pinfunction "CSR_DV/MODE2_11") (pintype "passive"))
    )
    (net (code "85") (name "/PA9") (class "Default")
      (node (ref "M1") (pin "51") (pinfunction "51_51") (pintype "passive"))
      (node (ref "P5") (pin "2") (pinfunction "2_2") (pintype "passive"))
      (node (ref "U4") (pin "4") (pinfunction "DI_4") (pintype "passive"))
    )
    (net (code "86") (name "/PA10") (class "Default")
      (node (ref "M1") (pin "52") (pinfunction "52_52") (pintype "passive"))
      (node (ref "P5") (pin "1") (pinfunction "1_1") (pintype "passive"))
      (node (ref "U4") (pin "1") (pinfunction "RO_1") (pintype "passive"))
    )
    (net (code "87") (name "/PA11") (class "Default")
      (node (ref "M1") (pin "53") (pinfunction "53_53") (pintype "passive"))
    )
    (net (code "88") (name "/PA12") (class "Default")
      (node (ref "M1") (pin "54") (pinfunction "54_54") (pintype "passive"))
    )
    (net (code "89") (name "/PB6") (class "Default")
      (node (ref "M1") (pin "24") (pinfunction "24_24") (pintype "passive"))
    )
    (net (code "90") (name "/PB13") (class "Default")
      (node (ref "M2") (pin "5") (pinfunction "5_5") (pintype "passive"))
    )
    (net (code "91") (name "/PB14") (class "Default")
      (node (ref "M2") (pin "6") (pinfunction "6_6") (pintype "passive"))
    )
    (net (code "92") (name "/PB15") (class "Default")
      (node (ref "M2") (pin "7") (pinfunction "7_7") (pintype "passive"))
    )
    (net (code "93") (name "/PC4") (class "Default")
      (node (ref "M1") (pin "49") (pinfunction "49_49") (pintype "passive"))
      (node (ref "U3") (pin "8") (pinfunction "RXD0/MODE0_8") (pintype "passive"))
    )
    (net (code "94") (name "/PC5") (class "Default")
      (node (ref "M1") (pin "50") (pinfunction "50_50") (pintype "passive"))
      (node (ref "U3") (pin "7") (pinfunction "RXD1/MODE1_7") (pintype "passive"))
    )
    (net (code "95") (name "/PC10") (class "Default")
      (node (ref "M1") (pin "40") (pinfunction "40_40") (pintype "passive"))
      (node (ref "R9") (pin "1") (pintype "passive"))
      (node (ref "SD_CARD1") (pin "9") (pinfunction "DATA2_9") (pintype "passive"))
    )
    (net (code "96") (name "/PC12") (class "Default")
      (node (ref "M1") (pin "38") (pinfunction "38_38") (pintype "passive"))
      (node (ref "SD_CARD1") (pin "5") (pinfunction "CLK_5") (pintype "passive"))
    )
    (net (code "97") (name "/PD2") (class "Default")
      (node (ref "M1") (pin "37") (pinfunction "37_37") (pintype "passive"))
      (node (ref "R12") (pin "1") (pintype "passive"))
      (node (ref "SD_CARD1") (pin "2") (pinfunction "CMD_2") (pintype "passive"))
    )
    (net (code "98") (name "/PE2") (class "Default")
      (node (ref "M1") (pin "20") (pinfunction "20_20") (pintype "passive"))
    )
    (net (code "99") (name "/PE3") (class "Default")
      (node (ref "M1") (pin "19") (pinfunction "19_19") (pintype "passive"))
    )
    (net (code "100") (name "/PE4") (class "Default")
      (node (ref "M1") (pin "18") (pinfunction "18_18") (pintype "passive"))
    )
    (net (code "101") (name "/PE5") (class "Default")
      (node (ref "M1") (pin "17") (pinfunction "17_17") (pintype "passive"))
    )
    (net (code "102") (name "/PE6") (class "Default")
      (node (ref "M1") (pin "16") (pinfunction "16_16") (pintype "passive"))
    )
    (net (code "103") (name "/PF6") (class "Default")
      (node (ref "M1") (pin "14") (pinfunction "14_14") (pintype "passive"))
    )
    (net (code "104") (name "/PF7") (class "Default")
      (node (ref "M1") (pin "13") (pinfunction "13_13") (pintype "passive"))
    )
    (net (code "105") (name "/PF8") (class "Default")
      (node (ref "M1") (pin "12") (pinfunction "12_12") (pintype "passive"))
    )
    (net (code "106") (name "/PF9") (class "Default")
      (node (ref "M1") (pin "11") (pinfunction "11_11") (pintype "passive"))
    )
    (net (code "107") (name "/PG3") (class "Default")
      (node (ref "M2") (pin "13") (pinfunction "13_13") (pintype "passive"))
    )
    (net (code "108") (name "/PG13") (class "Default")
      (node (ref "M1") (pin "33") (pinfunction "33_33") (pintype "passive"))
      (node (ref "U3") (pin "17") (pinfunction "TXD0_17") (pintype "passive"))
    )
    (net (code "109") (name "/PG14") (class "Default")
      (node (ref "M1") (pin "32") (pinfunction "32_32") (pintype "passive"))
      (node (ref "U3") (pin "18") (pinfunction "TXD1_18") (pintype "passive"))
    )
    (net (code "110") (name "/PH6") (class "Default")
      (node (ref "M2") (pin "8") (pinfunction "8_8") (pintype "passive"))
    )
    (net (code "111") (name "/PH7") (class "Default")
      (node (ref "M2") (pin "9") (pinfunction "9_9") (pintype "passive"))
    )
    (net (code "112") (name "/PI3") (class "Default")
      (node (ref "M2") (pin "41") (pinfunction "41_41") (pintype "passive"))
    )
    (net (code "113") (name "/PI8") (class "Default")
      (node (ref "M2") (pin "40") (pinfunction "40_40") (pintype "passive"))
    )
    (net (code "114") (name "/RESET") (class "Default")
      (node (ref "C24") (pin "2") (pintype "passive"))
      (node (ref "JTAG1") (pin "15") (pinfunction "RESET#_15") (pintype "passive"))
      (node (ref "M1") (pin "10") (pinfunction "10_10") (pintype "passive"))
      (node (ref "R29") (pin "1") (pintype "passive"))
    )
    (net (code "115") (name "/SPEED_LED") (class "Default")
      (node (ref "R13") (pin "1") (pintype "passive"))
      (node (ref "U3") (pin "2") (pinfunction "LED2/nINTSEL_2") (pintype "passive"))
    )
    (net (code "116") (name "/TPRX+") (class "Default")
      (node (ref "C19") (pin "2") (pintype "passive"))
      (node (ref "EARTHNET1") (pin "3") (pinfunction "RD+_3") (pintype "passive"))
      (node (ref "R7") (pin "1") (pintype "passive"))
      (node (ref "U3") (pin "23") (pinfunction "RXP_23") (pintype "passive"))
    )
    (net (code "117") (name "/TPRX-") (class "Default")
      (node (ref "C20") (pin "2") (pintype "passive"))
      (node (ref "EARTHNET1") (pin "6") (pinfunction "RD-_6") (pintype "passive"))
      (node (ref "R8") (pin "1") (pintype "passive"))
      (node (ref "U3") (pin "22") (pinfunction "RXN_22") (pintype "passive"))
    )
    (net (code "118") (name "/TPTX+") (class "Default")
      (node (ref "C17") (pin "2") (pintype "passive"))
      (node (ref "EARTHNET1") (pin "1") (pinfunction "TD+_1") (pintype "passive"))
      (node (ref "R5") (pin "1") (pintype "passive"))
      (node (ref "U3") (pin "21") (pinfunction "TXP_21") (pintype "passive"))
    )
    (net (code "119") (name "/TPTX-") (class "Default")
      (node (ref "C18") (pin "2") (pintype "passive"))
      (node (ref "EARTHNET1") (pin "2") (pinfunction "TD-_2") (pintype "passive"))
      (node (ref "R6") (pin "1") (pintype "passive"))
      (node (ref "U3") (pin "20") (pinfunction "TXN_20") (pintype "passive"))
    )
    (net (code "120") (name "/V5OUT") (class "Default")
      (node (ref "C2") (pin "1") (pinfunction "VCC_1") (pintype "passive"))
      (node (ref "K1") (pin "1") (pinfunction "1_1") (pintype "passive"))
      (node (ref "L1") (pin "2") (pinfunction "2_2") (pintype "passive"))
      (node (ref "U1") (pin "4") (pinfunction "FEEDBACK_4") (pintype "passive"))
    )
    (net (code "121") (name "/VBAT") (class "Default")
      (node (ref "C23") (pin "2") (pintype "passive"))
      (node (ref "D5") (pin "2") (pintype "passive"))
      (node (ref "D6") (pin "2") (pintype "passive"))
      (node (ref "M1") (pin "29") (pinfunction "29_29") (pintype "passive"))
    )
    (net (code "122") (name "/VREF+") (class "Default")
      (node (ref "M1") (pin "2") (pinfunction "2_2") (pintype "passive"))
      (node (ref "P1") (pin "1") (pinfunction "1_1") (pintype "passive"))
    )
    (net (code "123") (name "GND") (class "Default")
      (node (ref "BAT1") (pin "2") (pinfunction "GND_2") (pintype "passive"))
      (node (ref "BOOT1") (pin "5") (pinfunction "5_5") (pintype "passive"))
      (node (ref "BOOT1") (pin "6") (pinfunction "6_6") (pintype "passive"))
      (node (ref "C1") (pin "2") (pinfunction "GND_2") (pintype "passive"))
      (node (ref "C10") (pin "1") (pintype "passive"))
      (node (ref "C11") (pin "1") (pintype "passive"))
      (node (ref "C12") (pin "1") (pinfunction "1_1") (pintype "passive"))
      (node (ref "C13") (pin "1") (pintype "passive"))
      (node (ref "C14") (pin "1") (pintype "passive"))
      (node (ref "C15") (pin "1") (pintype "passive"))
      (node (ref "C16") (pin "1") (pintype "passive"))
      (node (ref "C17") (pin "1") (pintype "passive"))
      (node (ref "C18") (pin "1") (pintype "passive"))
      (node (ref "C19") (pin "1") (pintype "passive"))
      (node (ref "C2") (pin "2") (pinfunction "GND_2") (pintype "passive"))
      (node (ref "C20") (pin "1") (pintype "passive"))
      (node (ref "C21") (pin "2") (pintype "passive"))
      (node (ref "C23") (pin "1") (pintype "passive"))
      (node (ref "C24") (pin "1") (pintype "passive"))
      (node (ref "C25") (pin "1") (pinfunction "1_1") (pintype "passive"))
      (node (ref "C3") (pin "2") (pinfunction "2_2") (pintype "passive"))
      (node (ref "C4") (pin "1") (pintype "passive"))
      (node (ref "C5") (pin "2") (pintype "passive"))
      (node (ref "C6") (pin "1") (pintype "passive"))
      (node (ref "C7") (pin "1") (pintype "passive"))
      (node (ref "C8") (pin "1") (pintype "passive"))
      (node (ref "C9") (pin "1") (pintype "passive"))
      (node (ref "D2") (pin "1") (pinfunction "A_1") (pintype "passive"))
      (node (ref "D3") (pin "1") (pintype "passive"))
      (node (ref "D4") (pin "1") (pintype "passive"))
      (node (ref "DC_IN1") (pin "2") (pintype "passive"))
      (node (ref "DC_IN1") (pin "3") (pintype "passive"))
      (node (ref "EARTHNET1") (pin "13") (pinfunction "SHILED_13") (pintype "passive"))
      (node (ref "EARTHNET1") (pin "14") (pinfunction "SHILED_14") (pintype "passive"))
      (node (ref "EARTHNET1") (pin "8") (pinfunction "CHS_GND_8") (pintype "passive"))
      (node (ref "JTAG1") (pin "10") (pinfunction "GND_10") (pintype "passive"))
      (node (ref "JTAG1") (pin "12") (pinfunction "GND_12") (pintype "passive"))
      (node (ref "JTAG1") (pin "14") (pinfunction "GND_14") (pintype "passive"))
      (node (ref "JTAG1") (pin "16") (pinfunction "GND_16") (pintype "passive"))
      (node (ref "JTAG1") (pin "18") (pinfunction "GND_18") (pintype "passive"))
      (node (ref "JTAG1") (pin "20") (pinfunction "GND_20") (pintype "passive"))
      (node (ref "JTAG1") (pin "4") (pinfunction "GND_4") (pintype "passive"))
      (node (ref "JTAG1") (pin "6") (pinfunction "GND_6") (pintype "passive"))
      (node (ref "JTAG1") (pin "8") (pinfunction "GND_8") (pintype "passive"))
      (node (ref "M1") (pin "1") (pinfunction "1_1") (pintype "passive"))
      (node (ref "M1") (pin "30") (pinfunction "30_30") (pintype "passive"))
      (node (ref "M2") (pin "31") (pinfunction "31_31") (pintype "passive"))
      (node (ref "P2") (pin "1") (pinfunction "1_1") (pintype "passive"))
      (node (ref "P3") (pin "5") (pinfunction "5_5") (pintype "passive"))
      (node (ref "P4") (pin "10") (pinfunction "10_10") (pintype "passive"))
      (node (ref "P4") (pin "3") (pinfunction "3_3") (pintype "passive"))
      (node (ref "PWR1") (pin "2") (pinfunction "K_2") (pintype "passive"))
      (node (ref "R11") (pin "2") (pintype "passive"))
      (node (ref "R13") (pin "2") (pintype "passive"))
      (node (ref "R16") (pin "1") (pintype "passive"))
      (node (ref "R17") (pin "1") (pintype "passive"))
      (node (ref "R21") (pin "1") (pintype "passive"))
      (node (ref "R26") (pin "2") (pintype "passive"))
      (node (ref "RS1") (pin "8") (pinfunction "GND_8") (pintype "passive"))
      (node (ref "SD_CARD1") (pin "3") (pinfunction "VSS_3") (pintype "passive"))
      (node (ref "SD_CARD1") (pin "6") (pinfunction "VSS_6") (pintype "passive"))
      (node (ref "U1") (pin "3") (pintype "passive"))
      (node (ref "U1") (pin "5") (pintype "passive"))
      (node (ref "U2") (pin "1") (pinfunction "GND_1") (pintype "passive"))
      (node (ref "U3") (pin "25") (pinfunction "GND_25") (pintype "passive"))
      (node (ref "U4") (pin "5") (pinfunction "GND_5") (pintype "passive"))
      (node (ref "VOUT1") (pin "1") (pinfunction "1_1") (pintype "passive"))
      (node (ref "VOUT1") (pin "3") (pinfunction "3_3") (pintype "passive"))
      (node (ref "VOUT1") (pin "5") (pinfunction "5_5") (pintype "passive"))
      (node (ref "VOUT2") (pin "1") (pinfunction "1_1") (pintype "passive"))
      (node (ref "VOUT2") (pin "3") (pinfunction "3_3") (pintype "passive"))
      (node (ref "VOUT2") (pin "5") (pinfunction "5_5") (pintype "passive"))
    )
    (net (code "124") (name "Net-(BAT1-VCC)") (class "Default")
      (node (ref "BAT1") (pin "1") (pinfunction "VCC_1") (pintype "passive"))
      (node (ref "D6") (pin "1") (pintype "passive"))
    )
    (net (code "125") (name "Net-(BOOT1-Pad3)") (class "Default")
      (node (ref "BOOT1") (pin "3") (pinfunction "3_3") (pintype "passive"))
      (node (ref "R30") (pin "2") (pintype "passive"))
    )
    (net (code "126") (name "Net-(BOOT1-Pad4)") (class "Default")
      (node (ref "BOOT1") (pin "4") (pinfunction "4_4") (pintype "passive"))
      (node (ref "R31") (pin "1") (pintype "passive"))
    )
    (net (code "127") (name "Net-(C1-VCC)") (class "Default")
      (node (ref "C1") (pin "1") (pinfunction "VCC_1") (pintype "passive"))
      (node (ref "D1") (pin "1") (pinfunction "-_1") (pintype "passive"))
      (node (ref "U1") (pin "1") (pinfunction "IN_1") (pintype "passive"))
    )
    (net (code "128") (name "Net-(D1-+)") (class "Default")
      (node (ref "D1") (pin "2") (pinfunction "+_2") (pintype "passive"))
      (node (ref "F1") (pin "2") (pinfunction "2_2") (pintype "passive"))
    )
    (net (code "129") (name "Net-(D2-K)") (class "Default")
      (node (ref "D2") (pin "2") (pinfunction "K_2") (pintype "passive"))
      (node (ref "L1") (pin "1") (pinfunction "1_1") (pintype "passive"))
      (node (ref "U1") (pin "2") (pinfunction "OUTPUT_2") (pintype "passive"))
    )
    (net (code "130") (name "Net-(DS1-A)") (class "Default")
      (node (ref "DS1") (pin "1") (pinfunction "A_1") (pintype "passive"))
      (node (ref "R1") (pin "1") (pintype "passive"))
    )
    (net (code "131") (name "Net-(DS2-A)") (class "Default")
      (node (ref "DS2") (pin "1") (pinfunction "A_1") (pintype "passive"))
      (node (ref "R2") (pin "1") (pintype "passive"))
    )
    (net (code "132") (name "Net-(P1-Pad2)") (class "Default")
      (node (ref "P1") (pin "2") (pinfunction "2_2") (pintype "passive"))
      (node (ref "R32") (pin "2") (pintype "passive"))
    )
    (net (code "133") (name "Net-(PWR1-A)") (class "Default")
      (node (ref "PWR1") (pin "1") (pinfunction "A_1") (pintype "passive"))
      (node (ref "R3") (pin "1") (pintype "passive"))
    )
    (net (code "134") (name "Net-(RS1-A)") (class "Default")
      (node (ref "R27") (pin "1") (pintype "passive"))
      (node (ref "R28") (pin "2") (pintype "passive"))
      (node (ref "RS1") (pin "2") (pinfunction "A_2") (pintype "passive"))
      (node (ref "U4") (pin "6") (pinfunction "A_6") (pintype "passive"))
    )
    (net (code "135") (name "Net-(RS1-B)") (class "Default")
      (node (ref "R26") (pin "1") (pintype "passive"))
      (node (ref "R28") (pin "1") (pintype "passive"))
      (node (ref "RS1") (pin "4") (pinfunction "B_4") (pintype "passive"))
      (node (ref "U4") (pin "7") (pinfunction "B_7") (pintype "passive"))
    )
    (net (code "136") (name "Net-(U3-MDIO)") (class "Default")
      (node (ref "R4") (pin "2") (pintype "passive"))
      (node (ref "U3") (pin "12") (pinfunction "MDIO_12") (pintype "passive"))
    )
    (net (code "137") (name "Net-(U3-RBIAS)") (class "Default")
      (node (ref "R17") (pin "2") (pintype "passive"))
      (node (ref "U3") (pin "24") (pinfunction "RBIAS_24") (pintype "passive"))
    )
    (net (code "138") (name "Net-(U3-VDDCR)") (class "Default")
      (node (ref "C7") (pin "2") (pintype "passive"))
      (node (ref "C8") (pin "2") (pintype "passive"))
      (node (ref "U3") (pin "6") (pinfunction "VDDCR_6") (pintype "passive"))
    )
    (net (code "139") (name "Net-(U3-XTAL1{slash}CLKIN)") (class "Default")
      (node (ref "C13") (pin "2") (pintype "passive"))
      (node (ref "R18") (pin "2") (pintype "passive"))
      (node (ref "U3") (pin "5") (pinfunction "XTAL1/CLKIN_5") (pintype "passive"))
      (node (ref "Y1") (pin "2") (pinfunction "OSC2_2") (pintype "passive"))
    )
    (net (code "140") (name "Net-(U3-XTAL2)") (class "Default")
      (node (ref "C4") (pin "2") (pintype "passive"))
      (node (ref "R18") (pin "1") (pintype "passive"))
      (node (ref "U3") (pin "4") (pinfunction "XTAL2_4") (pintype "passive"))
      (node (ref "Y1") (pin "1") (pinfunction "OSC1_1") (pintype "passive"))
    )
    (net (code "141") (name "VCC3.3") (class "Default")
      (node (ref "BOOT1") (pin "1") (pinfunction "1_1") (pintype "passive"))
      (node (ref "BOOT1") (pin "2") (pinfunction "2_2") (pintype "passive"))
      (node (ref "C12") (pin "2") (pinfunction "2_2") (pintype "passive"))
      (node (ref "C14") (pin "2") (pintype "passive"))
      (node (ref "C21") (pin "1") (pintype "passive"))
      (node (ref "C25") (pin "2") (pinfunction "2_2") (pintype "passive"))
      (node (ref "C6") (pin "2") (pintype "passive"))
      (node (ref "C9") (pin "2") (pintype "passive"))
      (node (ref "D4") (pin "2") (pintype "passive"))
      (node (ref "D5") (pin "1") (pintype "passive"))
      (node (ref "JTAG1") (pin "1") (pinfunction "VDD_1") (pintype "passive"))
      (node (ref "JTAG1") (pin "2") (pinfunction "VDD_2") (pintype "passive"))
      (node (ref "L2") (pin "2") (pintype "passive"))
      (node (ref "R1") (pin "2") (pintype "passive"))
      (node (ref "R10") (pin "2") (pintype "passive"))
      (node (ref "R12") (pin "2") (pintype "passive"))
      (node (ref "R14") (pin "2") (pintype "passive"))
      (node (ref "R15") (pin "2") (pintype "passive"))
      (node (ref "R2") (pin "2") (pintype "passive"))
      (node (ref "R22") (pin "1") (pintype "passive"))
      (node (ref "R23") (pin "1") (pintype "passive"))
      (node (ref "R24") (pin "1") (pintype "passive"))
      (node (ref "R25") (pin "1") (pintype "passive"))
      (node (ref "R27") (pin "2") (pintype "passive"))
      (node (ref "R29") (pin "2") (pintype "passive"))
      (node (ref "R3") (pin "2") (pintype "passive"))
      (node (ref "R32") (pin "1") (pintype "passive"))
      (node (ref "R9") (pin "2") (pintype "passive"))
      (node (ref "SD_CARD1") (pin "4") (pinfunction "VDD_4") (pintype "passive"))
      (node (ref "U2") (pin "2") (pinfunction "OUT_2") (pintype "passive"))
      (node (ref "U2") (pin "4") (pinfunction "OUT_4") (pintype "passive"))
      (node (ref "U3") (pin "9") (pinfunction "VDDIO_9") (pintype "passive"))
      (node (ref "U4") (pin "8") (pinfunction "VCC_8") (pintype "passive"))
      (node (ref "VOUT1") (pin "2") (pinfunction "2_2") (pintype "passive"))
      (node (ref "VOUT1") (pin "4") (pinfunction "4_4") (pintype "passive"))
      (node (ref "VOUT1") (pin "6") (pinfunction "6_6") (pintype "passive"))
    )
    (net (code "142") (name "VCC3.3E") (class "Default")
      (node (ref "C10") (pin "2") (pintype "passive"))
      (node (ref "C11") (pin "2") (pintype "passive"))
      (node (ref "C15") (pin "2") (pintype "passive"))
      (node (ref "C16") (pin "2") (pintype "passive"))
      (node (ref "EARTHNET1") (pin "4") (pinfunction "TCT_4") (pintype "passive"))
      (node (ref "EARTHNET1") (pin "5") (pinfunction "RCT_5") (pintype "passive"))
      (node (ref "L2") (pin "1") (pintype "passive"))
      (node (ref "R5") (pin "2") (pintype "passive"))
      (node (ref "R6") (pin "2") (pintype "passive"))
      (node (ref "R7") (pin "2") (pintype "passive"))
      (node (ref "R8") (pin "2") (pintype "passive"))
      (node (ref "U3") (pin "1") (pinfunction "VDD2A_1") (pintype "passive"))
      (node (ref "U3") (pin "19") (pinfunction "VDD1A_19") (pintype "passive"))
    )
    (net (code "143") (name "VCC5") (class "Default")
      (node (ref "C3") (pin "1") (pinfunction "1_1") (pintype "passive"))
      (node (ref "C5") (pin "1") (pintype "passive"))
      (node (ref "D3") (pin "2") (pintype "passive"))
      (node (ref "K1") (pin "2") (pinfunction "2_2") (pintype "passive"))
      (node (ref "M1") (pin "58") (pinfunction "58_58") (pintype "passive"))
      (node (ref "M1") (pin "59") (pinfunction "59_59") (pintype "passive"))
      (node (ref "M1") (pin "60") (pinfunction "60_60") (pintype "passive"))
      (node (ref "P2") (pin "2") (pinfunction "2_2") (pintype "passive"))
      (node (ref "P3") (pin "6") (pinfunction "6_6") (pintype "passive"))
      (node (ref "P4") (pin "1") (pinfunction "1_1") (pintype "passive"))
      (node (ref "U2") (pin "3") (pinfunction "IN_3") (pintype "passive"))
      (node (ref "VOUT2") (pin "2") (pinfunction "2_2") (pintype "passive"))
      (node (ref "VOUT2") (pin "4") (pinfunction "4_4") (pintype "passive"))
      (node (ref "VOUT2") (pin "6") (pinfunction "6_6") (pintype "passive"))
    )
    (net (code "144") (name "VCC12") (class "Default")
      (node (ref "DC_IN1") (pin "1") (pintype "passive"))
      (node (ref "F1") (pin "1") (pinfunction "1_1") (pintype "passive"))
      (node (ref "RS1") (pin "1") (pinfunction "VCC_1") (pintype "passive"))
    )
    (net (code "145") (name "unconnected-(EARTHNET1-LED(G)_A-Pad9)") (class "Default")
      (node (ref "EARTHNET1") (pin "9") (pinfunction "LED(G)_A_9") (pintype "passive+no_connect"))
    )
    (net (code "146") (name "unconnected-(EARTHNET1-LED(G)_K-Pad10)") (class "Default")
      (node (ref "EARTHNET1") (pin "10") (pinfunction "LED(G)_K_10") (pintype "passive+no_connect"))
    )
    (net (code "147") (name "unconnected-(EARTHNET1-LED(Y)_A-Pad12)") (class "Default")
      (node (ref "EARTHNET1") (pin "12") (pinfunction "LED(Y)_A_12") (pintype "passive+no_connect"))
    )
    (net (code "148") (name "unconnected-(EARTHNET1-LED(Y)_K-Pad11)") (class "Default")
      (node (ref "EARTHNET1") (pin "11") (pinfunction "LED(Y)_K_11") (pintype "passive+no_connect"))
    )
    (net (code "149") (name "unconnected-(EARTHNET1-NC-Pad7)") (class "Default")
      (node (ref "EARTHNET1") (pin "7") (pinfunction "NC_7") (pintype "passive"))
    )
    (net (code "150") (name "unconnected-(JTAG1-NC-Pad11)") (class "Default")
      (node (ref "JTAG1") (pin "11") (pinfunction "NC_11") (pintype "passive"))
    )
    (net (code "151") (name "unconnected-(JTAG1-NC-Pad17)") (class "Default")
      (node (ref "JTAG1") (pin "17") (pinfunction "NC_17") (pintype "passive"))
    )
    (net (code "152") (name "unconnected-(JTAG1-NC-Pad19)") (class "Default")
      (node (ref "JTAG1") (pin "19") (pinfunction "NC_19") (pintype "passive"))
    )
    (net (code "153") (name "unconnected-(P2-Pad3)") (class "Default")
      (node (ref "P2") (pin "3") (pinfunction "3_3") (pintype "passive"))
    )
    (net (code "154") (name "unconnected-(P2-Pad6)") (class "Default")
      (node (ref "P2") (pin "6") (pinfunction "6_6") (pintype "passive"))
    )
    (net (code "155") (name "unconnected-(P2-Pad7)") (class "Default")
      (node (ref "P2") (pin "7") (pinfunction "7_7") (pintype "passive"))
    )
    (net (code "156") (name "unconnected-(P4-Pad2)") (class "Default")
      (node (ref "P4") (pin "2") (pinfunction "2_2") (pintype "passive"))
    )
    (net (code "157") (name "unconnected-(P4-Pad6)") (class "Default")
      (node (ref "P4") (pin "6") (pinfunction "6_6") (pintype "passive"))
    )
    (net (code "158") (name "unconnected-(P4-Pad7)") (class "Default")
      (node (ref "P4") (pin "7") (pinfunction "7_7") (pintype "passive"))
    )
    (net (code "159") (name "unconnected-(P4-Pad8)") (class "Default")
      (node (ref "P4") (pin "8") (pinfunction "8_8") (pintype "passive"))
    )
    (net (code "160") (name "unconnected-(P4-Pad9)") (class "Default")
      (node (ref "P4") (pin "9") (pinfunction "9_9") (pintype "passive"))
    )
    (net (code "161") (name "unconnected-(P4-Pad12)") (class "Default")
      (node (ref "P4") (pin "12") (pinfunction "12_12") (pintype "passive"))
    )
    (net (code "162") (name "unconnected-(P4-Pad13)") (class "Default")
      (node (ref "P4") (pin "13") (pinfunction "13_13") (pintype "passive"))
    )
    (net (code "163") (name "unconnected-(P4-Pad14)") (class "Default")
      (node (ref "P4") (pin "14") (pinfunction "14_14") (pintype "passive"))
    )
    (net (code "164") (name "unconnected-(P4-Pad15)") (class "Default")
      (node (ref "P4") (pin "15") (pinfunction "15_15") (pintype "passive"))
    )
    (net (code "165") (name "unconnected-(P4-Pad16)") (class "Default")
      (node (ref "P4") (pin "16") (pinfunction "16_16") (pintype "passive"))
    )
    (net (code "166") (name "unconnected-(RS1-NC-Pad3)") (class "Default")
      (node (ref "RS1") (pin "3") (pinfunction "NC_3") (pintype "passive"))
    )
    (net (code "167") (name "unconnected-(RS1-NC-Pad5)") (class "Default")
      (node (ref "RS1") (pin "5") (pinfunction "NC_5") (pintype "passive"))
    )
    (net (code "168") (name "unconnected-(RS1-NC-Pad6)") (class "Default")
      (node (ref "RS1") (pin "6") (pinfunction "NC_6") (pintype "passive"))
    )
    (net (code "169") (name "unconnected-(RS1-NC-Pad7)") (class "Default")
      (node (ref "RS1") (pin "7") (pinfunction "NC_7") (pintype "passive"))
    )
    (net (code "170") (name "unconnected-(SD_CARD1-CD-Pad10)") (class "Default")
      (node (ref "SD_CARD1") (pin "10") (pinfunction "CD_10") (pintype "passive"))
    )
    (net (code "171") (name "unconnected-(SD_CARD1-GND-Pad11)") (class "Default")
      (node (ref "SD_CARD1") (pin "11") (pinfunction "GND_11") (pintype "passive"))
    )
    (net (code "172") (name "unconnected-(SD_CARD1-WP-Pad12)") (class "Default")
      (node (ref "SD_CARD1") (pin "12") (pinfunction "WP_12") (pintype "passive"))
    )
    (net (code "173") (name "unconnected-(U3-RXER{slash}PHYAD0-Pad10)") (class "Default")
      (node (ref "U3") (pin "10") (pinfunction "RXER/PHYAD0_10") (pintype "passive"))
    )
  )
)
